# FULL_CB_Servo_REV_B.net
KiCad netlist of a schematic drawn in Altium Designer
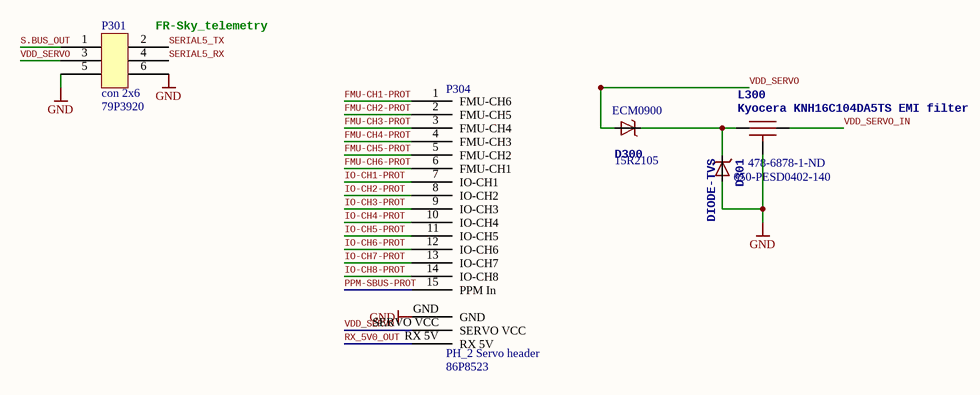
[diagram p0: FULL_CB_Servo_REV_B.SchDoc]

(export (version "E")
  (design (tool "Eeschema 10.0.6"))
  (components
    (comp (ref "D300")
      (value "MSS1P4-M3")
      (footprint "MICROSMP")
      (description "Diode, Schottky, 40V, 1A, MicroSMP, SMD")
      (fields (field (name "SUPPLIER PART NUMBER 1") "15R2105") (field (name "3DR_PARTNO") "ECM0900"))
      (libsource (lib "PCA_0005_FULL_CB_REV_A") (part "DIODE-SCHOTTKY_MSMP"))
    )
    (comp (ref "D301")
      (value "DIODE-TVS")
      (footprint "0402-TVS")
      (description "Diode, TVS, 14VWM, 40VC, 0402, SMD")
      (fields
        (field (name "SUPPLIER PART NUMBER 1") "650-PESD0402-140")
        (field (name "3DR_PARTNO") "ECM0837")
      )
      (libsource (lib "PCA_0005_FULL_CB_REV_A") (part "DIODE-TVS"))
    )
    (comp (ref "L300")
      (value "Kyocera KNH16C104DA5TS EMI filter")
      (footprint "KYOCERA-KNH16-DA")
      (description "Capacitor, Filter, 0.1uF, 25V, 2A, 0603, SMD")
      (fields (field (name "SUPPLIER PART NUMBER 1") "478-6878-1-ND") (field (name "3DR_PARTNO") "ECM0719"))
      (libsource (lib "PCA_0005_FULL_CB_REV_A") (part "KNH16C104DA5TS"))
    )
    (comp (ref "P301")
      (value "con 2x6")
      (footprint "TSW-103-07-G-D")
      (description "Connector, Header, 6Pos, 2.54MM, Vert, THT, Au")
      (fields (field (name "SUPPLIER PART NUMBER 1") "79P3920") (field (name "3DR_PARTNO") "PRT0445"))
      (libsource (lib "PCA_0005_FULL_CB_REV_A") (part "con 2x6"))
    )
    (comp (ref "P304")
      (value "PH_2 Servo header")
      (footprint "TSW-115-08-G-T-RA")
      (description "Connector, Header, 45Pos, 2.54MM, R/A, THT, Tin")
      (fields (field (name "SUPPLIER PART NUMBER 1") "86P8523") (field (name "3DR_PARTNO") "PRT0446"))
      (libsource (lib "PCA_0005_FULL_CB_REV_A") (part "PH_2 Servo header"))
    )
  )
  (nets
    (net (code "1") (name "/FMU-CH1-PROT") (class "Default")
      (node (ref "P304") (pin "1") (pinfunction "FMU-CH6_1") (pintype "passive"))
    )
    (net (code "2") (name "/FMU-CH2-PROT") (class "Default")
      (node (ref "P304") (pin "2") (pinfunction "FMU-CH5_2") (pintype "passive"))
    )
    (net (code "3") (name "/FMU-CH3-PROT") (class "Default")
      (node (ref "P304") (pin "3") (pinfunction "FMU-CH4_3") (pintype "passive"))
    )
    (net (code "4") (name "/FMU-CH4-PROT") (class "Default")
      (node (ref "P304") (pin "4") (pinfunction "FMU-CH3_4") (pintype "passive"))
    )
    (net (code "5") (name "/FMU-CH5-PROT") (class "Default")
      (node (ref "P304") (pin "5") (pinfunction "FMU-CH2_5") (pintype "passive"))
    )
    (net (code "6") (name "/FMU-CH6-PROT") (class "Default")
      (node (ref "P304") (pin "6") (pinfunction "FMU-CH1_6") (pintype "passive"))
    )
    (net (code "7") (name "/IO-CH1-PROT") (class "Default")
      (node (ref "P304") (pin "7") (pinfunction "IO-CH1_7") (pintype "passive"))
    )
    (net (code "8") (name "/IO-CH2-PROT") (class "Default")
      (node (ref "P304") (pin "8") (pinfunction "IO-CH2_8") (pintype "passive"))
    )
    (net (code "9") (name "/IO-CH3-PROT") (class "Default")
      (node (ref "P304") (pin "9") (pinfunction "IO-CH3_9") (pintype "passive"))
    )
    (net (code "10") (name "/IO-CH4-PROT") (class "Default")
      (node (ref "P304") (pin "10") (pinfunction "IO-CH4_10") (pintype "passive"))
    )
    (net (code "11") (name "/IO-CH5-PROT") (class "Default")
      (node (ref "P304") (pin "11") (pinfunction "IO-CH5_11") (pintype "passive"))
    )
    (net (code "12") (name "/IO-CH6-PROT") (class "Default")
      (node (ref "P304") (pin "12") (pinfunction "IO-CH6_12") (pintype "passive"))
    )
    (net (code "13") (name "/IO-CH7-PROT") (class "Default")
      (node (ref "P304") (pin "13") (pinfunction "IO-CH7_13") (pintype "passive"))
    )
    (net (code "14") (name "/IO-CH8-PROT") (class "Default")
      (node (ref "P304") (pin "14") (pinfunction "IO-CH8_14") (pintype "passive"))
    )
    (net (code "15") (name "/PPM-SBUS-PROT") (class "Default")
      (node (ref "P304") (pin "15") (pinfunction "PPM_In_15") (pintype "passive"))
    )
    (net (code "16") (name "/RX_5V0_OUT") (class "Default")
      (node (ref "P304") (pin "RX_5V") (pinfunction "RX_5V_RX_5V") (pintype "passive"))
    )
    (net (code "17") (name "/S.BUS_OUT") (class "Default")
      (node (ref "P301") (pin "1") (pinfunction "1_1") (pintype "passive"))
    )
    (net (code "18") (name "/SERIAL5_RX") (class "Default")
      (node (ref "P301") (pin "4") (pinfunction "4_4") (pintype "passive"))
    )
    (net (code "19") (name "/SERIAL5_TX") (class "Default")
      (node (ref "P301") (pin "2") (pinfunction "2_2") (pintype "passive"))
    )
    (net (code "20") (name "/VDD_SERVO") (class "Default")
      (node (ref "D300") (pin "ANODE") (pinfunction "A_ANODE") (pintype "passive"))
      (node (ref "P301") (pin "3") (pinfunction "3_3") (pintype "passive"))
      (node (ref "P304") (pin "SERVO_VCC") (pinfunction "SERVO_VCC_SERVO_VCC") (pintype "passive"))
    )
    (net (code "21") (name "/VDD_SERVO_IN") (class "Default")
      (node (ref "L300") (pin "P$2") (pinfunction "P$2_P$2") (pintype "passive"))
    )
    (net (code "22") (name "GND") (class "Default")
      (node (ref "D301") (pin "A") (pinfunction "A_A") (pintype "passive"))
      (node (ref "L300") (pin "GND") (pinfunction "GND_GND") (pintype "passive"))
      (node (ref "P301") (pin "5") (pinfunction "5_5") (pintype "passive"))
      (node (ref "P301") (pin "6") (pinfunction "6_6") (pintype "passive"))
      (node (ref "P304") (pin "GND") (pinfunction "GND_GND") (pintype "passive"))
    )
    (net (code "23") (name "Net-(D300-C)") (class "Default")
      (node (ref "D300") (pin "CATHODE") (pinfunction "C_CATHODE") (pintype "passive"))
      (node (ref "D301") (pin "C") (pinfunction "C_C") (pintype "passive"))
      (node (ref "L300") (pin "P$1") (pinfunction "P$1_P$1") (pintype "passive"))
    )
  )
)
